# S6.net
KiCad netlist of a schematic drawn in Altium Designer
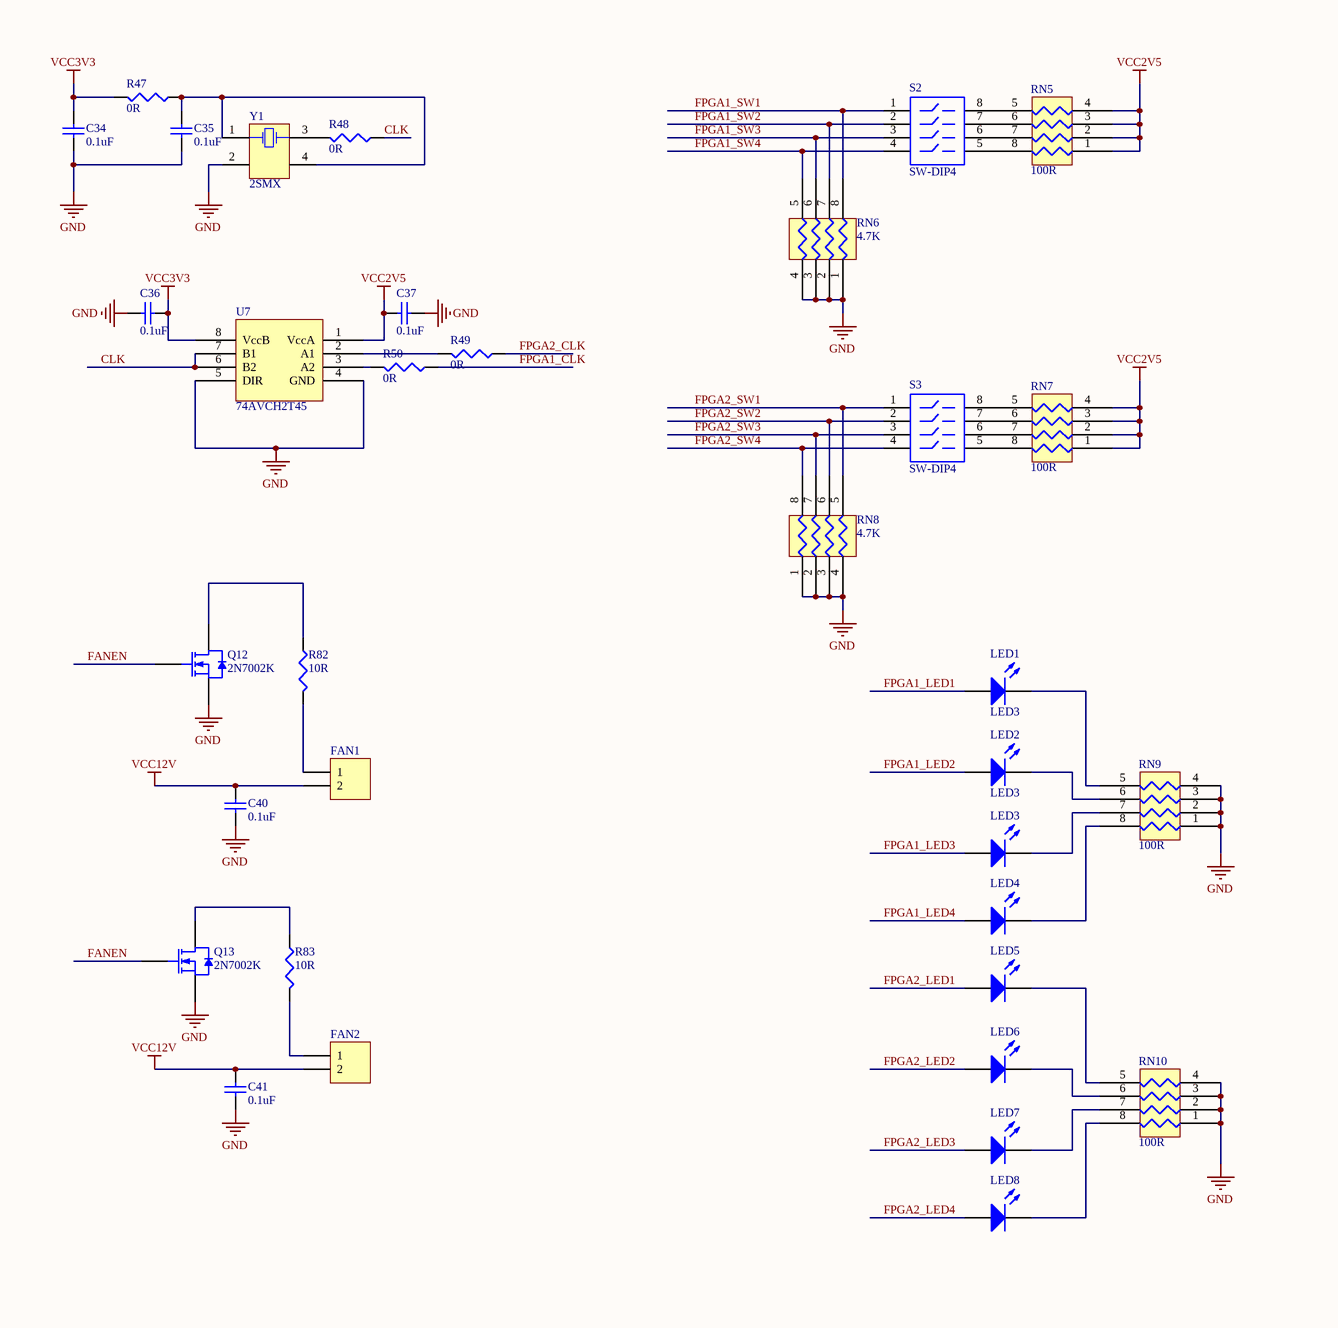
[diagram p0: S6.SchDoc, left]
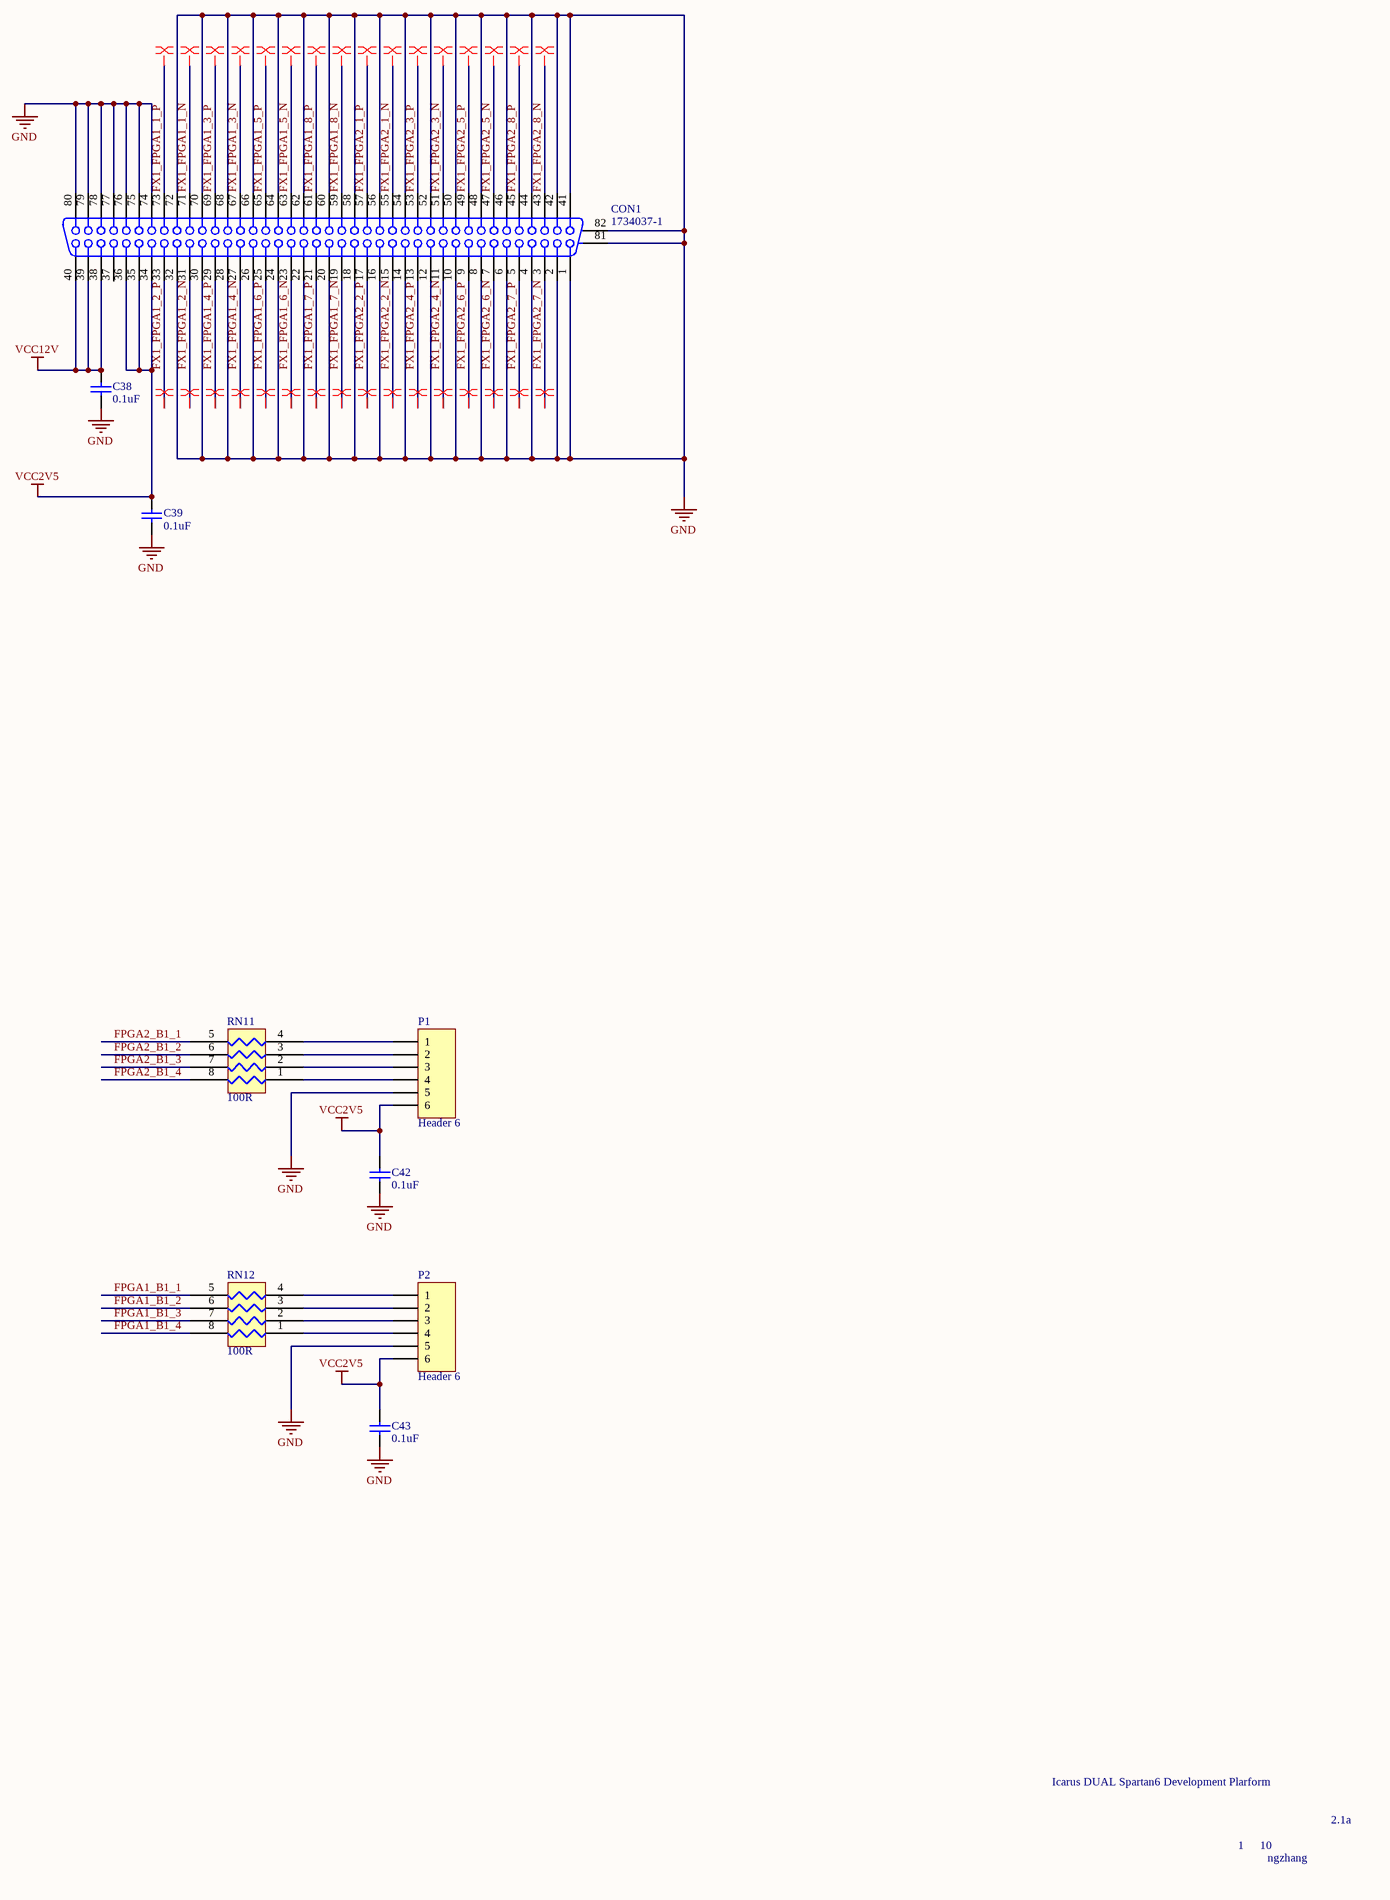
[diagram p1: S6.SchDoc, right]

(export (version "E")
  (design (tool "Eeschema 10.0.6"))
  (components
    (comp (ref "C34")
      (value "0.1uF")
      (footprint "1608[0603]")
      (description "Capacitor (Semiconductor SIM Model)")
      (fields (field (name "PUBLISHER") "Altium Limited"))
      (libsource (lib "Miscellaneous Devices") (part "Cap Semi"))
    )
    (comp (ref "C35")
      (value "0.1uF")
      (footprint "1608[0603]")
      (description "Capacitor (Semiconductor SIM Model)")
      (fields (field (name "PUBLISHER") "Altium Limited"))
      (libsource (lib "Miscellaneous Devices") (part "Cap Semi"))
    )
    (comp (ref "C36")
      (value "0.1uF")
      (footprint "1608[0603]")
      (description "Capacitor (Semiconductor SIM Model)")
      (fields (field (name "PUBLISHER") "Altium Limited"))
      (libsource (lib "Miscellaneous Devices") (part "Cap Semi"))
    )
    (comp (ref "C37")
      (value "0.1uF")
      (footprint "1608[0603]")
      (description "Capacitor (Semiconductor SIM Model)")
      (fields (field (name "PUBLISHER") "Altium Limited"))
      (libsource (lib "Miscellaneous Devices") (part "Cap Semi"))
    )
    (comp (ref "C38")
      (value "0.1uF")
      (footprint "1608[0603]")
      (description "Capacitor (Semiconductor SIM Model)")
      (fields (field (name "PUBLISHER") "Altium Limited"))
      (libsource (lib "Miscellaneous Devices") (part "Cap Semi"))
    )
    (comp (ref "C39")
      (value "0.1uF")
      (footprint "1608[0603]")
      (description "Capacitor (Semiconductor SIM Model)")
      (fields (field (name "PUBLISHER") "Altium Limited"))
      (libsource (lib "Miscellaneous Devices") (part "Cap Semi"))
    )
    (comp (ref "C40")
      (value "0.1uF")
      (footprint "1608[0603]")
      (description "Capacitor (Semiconductor SIM Model)")
      (fields (field (name "PUBLISHER") "Altium Limited"))
      (libsource (lib "Miscellaneous Devices") (part "Cap Semi"))
    )
    (comp (ref "C41")
      (value "0.1uF")
      (footprint "1608[0603]")
      (description "Capacitor (Semiconductor SIM Model)")
      (fields (field (name "PUBLISHER") "Altium Limited"))
      (libsource (lib "Miscellaneous Devices") (part "Cap Semi"))
    )
    (comp (ref "C42")
      (value "0.1uF")
      (footprint "1608[0603]")
      (description "Capacitor (Semiconductor SIM Model)")
      (fields (field (name "PUBLISHER") "Altium Limited"))
      (libsource (lib "Miscellaneous Devices") (part "Cap Semi"))
    )
    (comp (ref "C43")
      (value "0.1uF")
      (footprint "1608[0603]")
      (description "Capacitor (Semiconductor SIM Model)")
      (fields (field (name "PUBLISHER") "Altium Limited"))
      (libsource (lib "Miscellaneous Devices") (part "Cap Semi"))
    )
    (comp (ref "CON1") (value "1734037-1") (footprint "1734037-1") (libsource (lib "S6") (part "1734037-1")))
    (comp (ref "FAN1")
      (value "Header 2")
      (footprint "2PINFAN")
      (description "Header, 2-Pin")
      (fields (field (name "PUBLISHER") "Altium Limited"))
      (libsource (lib "Miscellaneous Connectors") (part "Header 2"))
    )
    (comp (ref "FAN2")
      (value "Header 2")
      (footprint "2PINFAN")
      (description "Header, 2-Pin")
      (fields (field (name "PUBLISHER") "Altium Limited"))
      (libsource (lib "Miscellaneous Connectors") (part "Header 2"))
    )
    (comp (ref "LED1")
      (value "LED3")
      (footprint "CD1608-0603")
      (description "Typical BLUE SiC LED")
      (fields (field (name "PUBLISHER") "Altium Limited"))
      (libsource (lib "Miscellaneous Devices") (part "LED3"))
    )
    (comp (ref "LED2")
      (value "LED3")
      (footprint "CD1608-0603")
      (description "Typical BLUE SiC LED")
      (fields (field (name "PUBLISHER") "Altium Limited"))
      (libsource (lib "Miscellaneous Devices") (part "LED3"))
    )
    (comp (ref "LED3")
      (value "LED3")
      (footprint "CD1608-0603")
      (description "Typical BLUE SiC LED")
      (fields (field (name "PUBLISHER") "Altium Limited"))
      (libsource (lib "Miscellaneous Devices") (part "LED3"))
    )
    (comp (ref "LED4")
      (value "LED3")
      (footprint "CD1608-0603")
      (description "Typical BLUE SiC LED")
      (fields (field (name "PUBLISHER") "Altium Limited"))
      (libsource (lib "Miscellaneous Devices") (part "LED3"))
    )
    (comp (ref "LED5")
      (value "LED3")
      (footprint "CD1608-0603")
      (description "Typical BLUE SiC LED")
      (fields (field (name "PUBLISHER") "Altium Limited"))
      (libsource (lib "Miscellaneous Devices") (part "LED3"))
    )
    (comp (ref "LED6")
      (value "LED3")
      (footprint "CD1608-0603")
      (description "Typical BLUE SiC LED")
      (fields (field (name "PUBLISHER") "Altium Limited"))
      (libsource (lib "Miscellaneous Devices") (part "LED3"))
    )
    (comp (ref "LED7")
      (value "LED3")
      (footprint "CD1608-0603")
      (description "Typical BLUE SiC LED")
      (fields (field (name "PUBLISHER") "Altium Limited"))
      (libsource (lib "Miscellaneous Devices") (part "LED3"))
    )
    (comp (ref "LED8")
      (value "LED3")
      (footprint "CD1608-0603")
      (description "Typical BLUE SiC LED")
      (fields (field (name "PUBLISHER") "Altium Limited"))
      (libsource (lib "Miscellaneous Devices") (part "LED3"))
    )
    (comp (ref "P1")
      (value "Header 6")
      (footprint "HDR1X6")
      (description "Header, 6-Pin")
      (fields (field (name "PUBLISHER") "Altium Limited"))
      (libsource (lib "Miscellaneous Connectors") (part "Header 6"))
    )
    (comp (ref "P2")
      (value "Header 6")
      (footprint "HDR1X6")
      (description "Header, 6-Pin")
      (fields (field (name "PUBLISHER") "Altium Limited"))
      (libsource (lib "Miscellaneous Connectors") (part "Header 6"))
    )
    (comp (ref "Q12")
      (value "2N7002K")
      (footprint "SOT23_N")
      (description "N-channel Enhancement Mode Field-effect Transistor")
      (fields (field (name "PUBLISHER") "Altium Limited"))
      (libsource (lib "Philips Discrete MOSFET - Low Power") (part "2N7002"))
    )
    (comp (ref "Q13")
      (value "2N7002K")
      (footprint "SOT23_N")
      (description "N-channel Enhancement Mode Field-effect Transistor")
      (fields (field (name "PUBLISHER") "Altium Limited"))
      (libsource (lib "Philips Discrete MOSFET - Low Power") (part "2N7002"))
    )
    (comp (ref "R47")
      (value "0R")
      (footprint "J1-0603")
      (description "Resistor")
      (fields (field (name "PUBLISHER") "Altium Limited"))
      (libsource (lib "Miscellaneous Devices") (part "Res3"))
    )
    (comp (ref "R48")
      (value "0R")
      (footprint "J1-0603")
      (description "Resistor")
      (fields (field (name "PUBLISHER") "Altium Limited"))
      (libsource (lib "Miscellaneous Devices") (part "Res3"))
    )
    (comp (ref "R49")
      (value "0R")
      (footprint "J1-0603")
      (description "Resistor")
      (fields (field (name "PUBLISHER") "Altium Limited"))
      (libsource (lib "Miscellaneous Devices") (part "Res3"))
    )
    (comp (ref "R50")
      (value "0R")
      (footprint "J1-0603")
      (description "Resistor")
      (fields (field (name "PUBLISHER") "Altium Limited"))
      (libsource (lib "Miscellaneous Devices") (part "Res3"))
    )
    (comp (ref "R82")
      (value "10R")
      (footprint "J1-0603")
      (description "Resistor")
      (fields (field (name "PUBLISHER") "Altium Limited"))
      (libsource (lib "Miscellaneous Devices") (part "Res3"))
    )
    (comp (ref "R83")
      (value "10R")
      (footprint "J1-0603")
      (description "Resistor")
      (fields (field (name "PUBLISHER") "Altium Limited"))
      (libsource (lib "Miscellaneous Devices") (part "Res3"))
    )
    (comp (ref "RN5") (value "100R") (footprint "EXBV8V") (libsource (lib "S6") (part "RES4PACK")))
    (comp (ref "RN6") (value "4.7K") (footprint "EXBV8V") (libsource (lib "") (part "RES4PACK_2")))
    (comp (ref "RN7") (value "100R") (footprint "EXBV8V") (libsource (lib "S6") (part "RES4PACK")))
    (comp (ref "RN8") (value "4.7K") (footprint "EXBV8V") (libsource (lib "") (part "RES4PACK_1")))
    (comp (ref "RN9") (value "100R") (footprint "EXBV8V") (libsource (lib "S6") (part "RES4PACK")))
    (comp (ref "RN10") (value "100R") (footprint "EXBV8V") (libsource (lib "S6") (part "RES4PACK")))
    (comp (ref "RN11") (value "100R") (footprint "EXBV8V") (libsource (lib "S6") (part "RES4PACK")))
    (comp (ref "RN12") (value "100R") (footprint "EXBV8V") (libsource (lib "S6") (part "RES4PACK")))
    (comp (ref "S2")
      (value "SW-DIP4")
      (footprint "SO8_N")
      (description "DIP Switch")
      (fields (field (name "PUBLISHER") "Altium Limited"))
      (libsource (lib "Miscellaneous Devices") (part "SW-DIP4"))
    )
    (comp (ref "S3")
      (value "SW-DIP4")
      (footprint "SO8_N")
      (description "DIP Switch")
      (fields (field (name "PUBLISHER") "Altium Limited"))
      (libsource (lib "Miscellaneous Devices") (part "SW-DIP4"))
    )
    (comp (ref "U7") (value "74AVCH2T45") (footprint "SOT765-1") (libsource (lib "S6") (part "74AVCH2T45")))
    (comp (ref "Y1")
      (value "2SMX")
      (footprint "SMX2")
      (description "Surface Mount Quartz Crystal")
      (fields (field (name "PUBLISHER") "Altium Limited"))
      (libsource (lib "C-MAC Crystal Oscillator") (part "2SMX"))
    )
  )
  (nets
    (net (code "1") (name "/CLK") (class "Default")
      (node (ref "R48") (pin "1") (pinfunction "1_1") (pintype "passive"))
      (node (ref "U7") (pin "6") (pinfunction "B2_6") (pintype "passive"))
      (node (ref "U7") (pin "7") (pinfunction "B1_7") (pintype "passive"))
    )
    (net (code "2") (name "/FANEN") (class "Default")
      (node (ref "Q12") (pin "1") (pinfunction "G_1") (pintype "passive"))
      (node (ref "Q13") (pin "1") (pinfunction "G_1") (pintype "passive"))
    )
    (net (code "3") (name "/FPGA1_B1_1") (class "Default")
      (node (ref "RN12") (pin "5") (pinfunction "5_5") (pintype "power_in"))
    )
    (net (code "4") (name "/FPGA1_B1_2") (class "Default")
      (node (ref "RN12") (pin "6") (pinfunction "6_6") (pintype "power_in"))
    )
    (net (code "5") (name "/FPGA1_B1_3") (class "Default")
      (node (ref "RN12") (pin "7") (pinfunction "7_7") (pintype "power_in"))
    )
    (net (code "6") (name "/FPGA1_B1_4") (class "Default")
      (node (ref "RN12") (pin "8") (pinfunction "8_8") (pintype "power_in"))
    )
    (net (code "7") (name "/FPGA1_CLK") (class "Default")
      (node (ref "R50") (pin "1") (pinfunction "1_1") (pintype "passive"))
    )
    (net (code "8") (name "/FPGA1_LED1") (class "Default")
      (node (ref "LED1") (pin "1") (pinfunction "A_1") (pintype "passive"))
    )
    (net (code "9") (name "/FPGA1_LED2") (class "Default")
      (node (ref "LED2") (pin "1") (pinfunction "A_1") (pintype "passive"))
    )
    (net (code "10") (name "/FPGA1_LED3") (class "Default")
      (node (ref "LED3") (pin "1") (pinfunction "A_1") (pintype "passive"))
    )
    (net (code "11") (name "/FPGA1_LED4") (class "Default")
      (node (ref "LED4") (pin "1") (pinfunction "A_1") (pintype "passive"))
    )
    (net (code "12") (name "/FPGA1_SW1") (class "Default")
      (node (ref "RN6") (pin "8") (pinfunction "8_8") (pintype "power_in"))
      (node (ref "S2") (pin "1") (pinfunction "1_1") (pintype "passive"))
    )
    (net (code "13") (name "/FPGA1_SW2") (class "Default")
      (node (ref "RN6") (pin "7") (pinfunction "7_7") (pintype "power_in"))
      (node (ref "S2") (pin "2") (pinfunction "2_2") (pintype "passive"))
    )
    (net (code "14") (name "/FPGA1_SW3") (class "Default")
      (node (ref "RN6") (pin "6") (pinfunction "6_6") (pintype "power_in"))
      (node (ref "S2") (pin "3") (pinfunction "3_3") (pintype "passive"))
    )
    (net (code "15") (name "/FPGA1_SW4") (class "Default")
      (node (ref "RN6") (pin "5") (pinfunction "5_5") (pintype "power_in"))
      (node (ref "S2") (pin "4") (pinfunction "4_4") (pintype "passive"))
    )
    (net (code "16") (name "/FPGA2_B1_1") (class "Default")
      (node (ref "RN11") (pin "5") (pinfunction "5_5") (pintype "power_in"))
    )
    (net (code "17") (name "/FPGA2_B1_2") (class "Default")
      (node (ref "RN11") (pin "6") (pinfunction "6_6") (pintype "power_in"))
    )
    (net (code "18") (name "/FPGA2_B1_3") (class "Default")
      (node (ref "RN11") (pin "7") (pinfunction "7_7") (pintype "power_in"))
    )
    (net (code "19") (name "/FPGA2_B1_4") (class "Default")
      (node (ref "RN11") (pin "8") (pinfunction "8_8") (pintype "power_in"))
    )
    (net (code "20") (name "/FPGA2_CLK") (class "Default")
      (node (ref "R49") (pin "1") (pinfunction "1_1") (pintype "passive"))
    )
    (net (code "21") (name "/FPGA2_LED1") (class "Default")
      (node (ref "LED5") (pin "1") (pinfunction "A_1") (pintype "passive"))
    )
    (net (code "22") (name "/FPGA2_LED2") (class "Default")
      (node (ref "LED6") (pin "1") (pinfunction "A_1") (pintype "passive"))
    )
    (net (code "23") (name "/FPGA2_LED3") (class "Default")
      (node (ref "LED7") (pin "1") (pinfunction "A_1") (pintype "passive"))
    )
    (net (code "24") (name "/FPGA2_LED4") (class "Default")
      (node (ref "LED8") (pin "1") (pinfunction "A_1") (pintype "passive"))
    )
    (net (code "25") (name "/FPGA2_SW1") (class "Default")
      (node (ref "RN8") (pin "5") (pinfunction "5_5") (pintype "power_in"))
      (node (ref "S3") (pin "1") (pinfunction "1_1") (pintype "passive"))
    )
    (net (code "26") (name "/FPGA2_SW2") (class "Default")
      (node (ref "RN8") (pin "6") (pinfunction "6_6") (pintype "power_in"))
      (node (ref "S3") (pin "2") (pinfunction "2_2") (pintype "passive"))
    )
    (net (code "27") (name "/FPGA2_SW3") (class "Default")
      (node (ref "RN8") (pin "7") (pinfunction "7_7") (pintype "power_in"))
      (node (ref "S3") (pin "3") (pinfunction "3_3") (pintype "passive"))
    )
    (net (code "28") (name "/FPGA2_SW4") (class "Default")
      (node (ref "RN8") (pin "8") (pinfunction "8_8") (pintype "power_in"))
      (node (ref "S3") (pin "4") (pinfunction "4_4") (pintype "passive"))
    )
    (net (code "29") (name "/FX1_FPGA1_1_N") (class "Default")
      (node (ref "CON1") (pin "71") (pinfunction "71_71") (pintype "passive"))
    )
    (net (code "30") (name "/FX1_FPGA1_1_P") (class "Default")
      (node (ref "CON1") (pin "73") (pinfunction "73_73") (pintype "passive"))
    )
    (net (code "31") (name "/FX1_FPGA1_2_N") (class "Default")
      (node (ref "CON1") (pin "31") (pinfunction "31_31") (pintype "passive"))
    )
    (net (code "32") (name "/FX1_FPGA1_2_P") (class "Default")
      (node (ref "CON1") (pin "33") (pinfunction "33_33") (pintype "passive"))
    )
    (net (code "33") (name "/FX1_FPGA1_3_N") (class "Default")
      (node (ref "CON1") (pin "67") (pinfunction "67_67") (pintype "passive"))
    )
    (net (code "34") (name "/FX1_FPGA1_3_P") (class "Default")
      (node (ref "CON1") (pin "69") (pinfunction "69_69") (pintype "passive"))
    )
    (net (code "35") (name "/FX1_FPGA1_4_N") (class "Default")
      (node (ref "CON1") (pin "27") (pinfunction "27_27") (pintype "passive"))
    )
    (net (code "36") (name "/FX1_FPGA1_4_P") (class "Default")
      (node (ref "CON1") (pin "29") (pinfunction "29_29") (pintype "passive"))
    )
    (net (code "37") (name "/FX1_FPGA1_5_N") (class "Default")
      (node (ref "CON1") (pin "63") (pinfunction "63_63") (pintype "passive"))
    )
    (net (code "38") (name "/FX1_FPGA1_5_P") (class "Default")
      (node (ref "CON1") (pin "65") (pinfunction "65_65") (pintype "passive"))
    )
    (net (code "39") (name "/FX1_FPGA1_6_N") (class "Default")
      (node (ref "CON1") (pin "23") (pinfunction "23_23") (pintype "passive"))
    )
    (net (code "40") (name "/FX1_FPGA1_6_P") (class "Default")
      (node (ref "CON1") (pin "25") (pinfunction "25_25") (pintype "passive"))
    )
    (net (code "41") (name "/FX1_FPGA1_7_N") (class "Default")
      (node (ref "CON1") (pin "19") (pinfunction "19_19") (pintype "passive"))
    )
    (net (code "42") (name "/FX1_FPGA1_7_P") (class "Default")
      (node (ref "CON1") (pin "21") (pinfunction "21_21") (pintype "passive"))
    )
    (net (code "43") (name "/FX1_FPGA1_8_N") (class "Default")
      (node (ref "CON1") (pin "59") (pinfunction "59_59") (pintype "passive"))
    )
    (net (code "44") (name "/FX1_FPGA1_8_P") (class "Default")
      (node (ref "CON1") (pin "61") (pinfunction "61_61") (pintype "passive"))
    )
    (net (code "45") (name "/FX1_FPGA2_1_N") (class "Default")
      (node (ref "CON1") (pin "55") (pinfunction "55_55") (pintype "passive"))
    )
    (net (code "46") (name "/FX1_FPGA2_1_P") (class "Default")
      (node (ref "CON1") (pin "57") (pinfunction "57_57") (pintype "passive"))
    )
    (net (code "47") (name "/FX1_FPGA2_2_N") (class "Default")
      (node (ref "CON1") (pin "15") (pinfunction "15_15") (pintype "passive"))
    )
    (net (code "48") (name "/FX1_FPGA2_2_P") (class "Default")
      (node (ref "CON1") (pin "17") (pinfunction "17_17") (pintype "passive"))
    )
    (net (code "49") (name "/FX1_FPGA2_3_N") (class "Default")
      (node (ref "CON1") (pin "51") (pinfunction "51_51") (pintype "passive"))
    )
    (net (code "50") (name "/FX1_FPGA2_3_P") (class "Default")
      (node (ref "CON1") (pin "53") (pinfunction "53_53") (pintype "passive"))
    )
    (net (code "51") (name "/FX1_FPGA2_4_N") (class "Default")
      (node (ref "CON1") (pin "11") (pinfunction "11_11") (pintype "passive"))
    )
    (net (code "52") (name "/FX1_FPGA2_4_P") (class "Default")
      (node (ref "CON1") (pin "13") (pinfunction "13_13") (pintype "passive"))
    )
    (net (code "53") (name "/FX1_FPGA2_5_N") (class "Default")
      (node (ref "CON1") (pin "47") (pinfunction "47_47") (pintype "passive"))
    )
    (net (code "54") (name "/FX1_FPGA2_5_P") (class "Default")
      (node (ref "CON1") (pin "49") (pinfunction "49_49") (pintype "passive"))
    )
    (net (code "55") (name "/FX1_FPGA2_6_N") (class "Default")
      (node (ref "CON1") (pin "7") (pinfunction "7_7") (pintype "passive"))
    )
    (net (code "56") (name "/FX1_FPGA2_6_P") (class "Default")
      (node (ref "CON1") (pin "9") (pinfunction "9_9") (pintype "passive"))
    )
    (net (code "57") (name "/FX1_FPGA2_7_N") (class "Default")
      (node (ref "CON1") (pin "3") (pinfunction "3_3") (pintype "passive"))
    )
    (net (code "58") (name "/FX1_FPGA2_7_P") (class "Default")
      (node (ref "CON1") (pin "5") (pinfunction "5_5") (pintype "passive"))
    )
    (net (code "59") (name "/FX1_FPGA2_8_N") (class "Default")
      (node (ref "CON1") (pin "43") (pinfunction "43_43") (pintype "passive"))
    )
    (net (code "60") (name "/FX1_FPGA2_8_P") (class "Default")
      (node (ref "CON1") (pin "45") (pinfunction "45_45") (pintype "passive"))
    )
    (net (code "61") (name "GND") (class "Default")
      (node (ref "C34") (pin "1") (pinfunction "1_1") (pintype "passive"))
      (node (ref "C35") (pin "1") (pinfunction "1_1") (pintype "passive"))
      (node (ref "C36") (pin "2") (pinfunction "2_2") (pintype "passive"))
      (node (ref "C37") (pin "1") (pinfunction "1_1") (pintype "passive"))
      (node (ref "C38") (pin "1") (pinfunction "1_1") (pintype "passive"))
      (node (ref "C39") (pin "1") (pinfunction "1_1") (pintype "passive"))
      (node (ref "C40") (pin "2") (pinfunction "2_2") (pintype "passive"))
      (node (ref "C41") (pin "2") (pinfunction "2_2") (pintype "passive"))
      (node (ref "C42") (pin "1") (pinfunction "1_1") (pintype "passive"))
      (node (ref "C43") (pin "1") (pinfunction "1_1") (pintype "passive"))
      (node (ref "CON1") (pin "1") (pinfunction "1_1") (pintype "passive"))
      (node (ref "CON1") (pin "10") (pinfunction "10_10") (pintype "passive"))
      (node (ref "CON1") (pin "12") (pinfunction "12_12") (pintype "passive"))
      (node (ref "CON1") (pin "14") (pinfunction "14_14") (pintype "passive"))
      (node (ref "CON1") (pin "16") (pinfunction "16_16") (pintype "passive"))
      (node (ref "CON1") (pin "18") (pinfunction "18_18") (pintype "passive"))
      (node (ref "CON1") (pin "2") (pinfunction "2_2") (pintype "passive"))
      (node (ref "CON1") (pin "20") (pinfunction "20_20") (pintype "passive"))
      (node (ref "CON1") (pin "22") (pinfunction "22_22") (pintype "passive"))
      (node (ref "CON1") (pin "24") (pinfunction "24_24") (pintype "passive"))
      (node (ref "CON1") (pin "26") (pinfunction "26_26") (pintype "passive"))
      (node (ref "CON1") (pin "28") (pinfunction "28_28") (pintype "passive"))
      (node (ref "CON1") (pin "30") (pinfunction "30_30") (pintype "passive"))
      (node (ref "CON1") (pin "32") (pinfunction "32_32") (pintype "passive"))
      (node (ref "CON1") (pin "4") (pinfunction "4_4") (pintype "passive"))
      (node (ref "CON1") (pin "41") (pinfunction "41_41") (pintype "passive"))
      (node (ref "CON1") (pin "42") (pinfunction "42_42") (pintype "passive"))
      (node (ref "CON1") (pin "44") (pinfunction "44_44") (pintype "passive"))
      (node (ref "CON1") (pin "46") (pinfunction "46_46") (pintype "passive"))
      (node (ref "CON1") (pin "48") (pinfunction "48_48") (pintype "passive"))
      (node (ref "CON1") (pin "50") (pinfunction "50_50") (pintype "passive"))
      (node (ref "CON1") (pin "52") (pinfunction "52_52") (pintype "passive"))
      (node (ref "CON1") (pin "54") (pinfunction "54_54") (pintype "passive"))
      (node (ref "CON1") (pin "56") (pinfunction "56_56") (pintype "passive"))
      (node (ref "CON1") (pin "58") (pinfunction "58_58") (pintype "passive"))
      (node (ref "CON1") (pin "6") (pinfunction "6_6") (pintype "passive"))
      (node (ref "CON1") (pin "60") (pinfunction "60_60") (pintype "passive"))
      (node (ref "CON1") (pin "62") (pinfunction "62_62") (pintype "passive"))
      (node (ref "CON1") (pin "64") (pinfunction "64_64") (pintype "passive"))
      (node (ref "CON1") (pin "66") (pinfunction "66_66") (pintype "passive"))
      (node (ref "CON1") (pin "68") (pinfunction "68_68") (pintype "passive"))
      (node (ref "CON1") (pin "70") (pinfunction "70_70") (pintype "passive"))
      (node (ref "CON1") (pin "72") (pinfunction "72_72") (pintype "passive"))
      (node (ref "CON1") (pin "74") (pinfunction "74_74") (pintype "passive"))
      (node (ref "CON1") (pin "75") (pinfunction "75_75") (pintype "passive"))
      (node (ref "CON1") (pin "76") (pinfunction "76_76") (pintype "passive"))
      (node (ref "CON1") (pin "77") (pinfunction "77_77") (pintype "passive"))
      (node (ref "CON1") (pin "78") (pinfunction "78_78") (pintype "passive"))
      (node (ref "CON1") (pin "79") (pinfunction "79_79") (pintype "passive"))
      (node (ref "CON1") (pin "8") (pinfunction "8_8") (pintype "passive"))
      (node (ref "CON1") (pin "80") (pinfunction "80_80") (pintype "passive"))
      (node (ref "CON1") (pin "81") (pinfunction "MH1_81") (pintype "passive"))
      (node (ref "CON1") (pin "82") (pinfunction "MH2_82") (pintype "passive"))
      (node (ref "P1") (pin "5") (pinfunction "5_5") (pintype "passive"))
      (node (ref "P2") (pin "5") (pinfunction "5_5") (pintype "passive"))
      (node (ref "Q12") (pin "2") (pinfunction "S_2") (pintype "passive"))
      (node (ref "Q13") (pin "2") (pinfunction "S_2") (pintype "passive"))
      (node (ref "RN10") (pin "1") (pinfunction "1_1") (pintype "power_in"))
      (node (ref "RN10") (pin "2") (pinfunction "2_2") (pintype "power_in"))
      (node (ref "RN10") (pin "3") (pinfunction "3_3") (pintype "power_in"))
      (node (ref "RN10") (pin "4") (pinfunction "4_4") (pintype "power_in"))
      (node (ref "RN6") (pin "1") (pinfunction "1_1") (pintype "power_in"))
      (node (ref "RN6") (pin "2") (pinfunction "2_2") (pintype "power_in"))
      (node (ref "RN6") (pin "3") (pinfunction "3_3") (pintype "power_in"))
      (node (ref "RN6") (pin "4") (pinfunction "4_4") (pintype "power_in"))
      (node (ref "RN8") (pin "1") (pinfunction "1_1") (pintype "power_in"))
      (node (ref "RN8") (pin "2") (pinfunction "2_2") (pintype "power_in"))
      (node (ref "RN8") (pin "3") (pinfunction "3_3") (pintype "power_in"))
      (node (ref "RN8") (pin "4") (pinfunction "4_4") (pintype "power_in"))
      (node (ref "RN9") (pin "1") (pinfunction "1_1") (pintype "power_in"))
      (node (ref "RN9") (pin "2") (pinfunction "2_2") (pintype "power_in"))
      (node (ref "RN9") (pin "3") (pinfunction "3_3") (pintype "power_in"))
      (node (ref "RN9") (pin "4") (pinfunction "4_4") (pintype "power_in"))
      (node (ref "U7") (pin "4") (pinfunction "GND_4") (pintype "passive"))
      (node (ref "U7") (pin "5") (pinfunction "DIR_5") (pintype "passive"))
      (node (ref "Y1") (pin "2") (pinfunction "NC_2") (pintype "passive"))
    )
    (net (code "62") (name "Net-(FAN1-Pad1)") (class "Default")
      (node (ref "FAN1") (pin "1") (pinfunction "1_1") (pintype "passive"))
      (node (ref "R82") (pin "2") (pinfunction "2_2") (pintype "passive"))
    )
    (net (code "63") (name "Net-(FAN2-Pad1)") (class "Default")
      (node (ref "FAN2") (pin "1") (pinfunction "1_1") (pintype "passive"))
      (node (ref "R83") (pin "2") (pinfunction "2_2") (pintype "passive"))
    )
    (net (code "64") (name "Net-(LED1-K)") (class "Default")
      (node (ref "LED1") (pin "2") (pinfunction "K_2") (pintype "passive"))
      (node (ref "RN9") (pin "5") (pinfunction "5_5") (pintype "power_in"))
    )
    (net (code "65") (name "Net-(LED2-K)") (class "Default")
      (node (ref "LED2") (pin "2") (pinfunction "K_2") (pintype "passive"))
      (node (ref "RN9") (pin "6") (pinfunction "6_6") (pintype "power_in"))
    )
    (net (code "66") (name "Net-(LED3-K)") (class "Default")
      (node (ref "LED3") (pin "2") (pinfunction "K_2") (pintype "passive"))
      (node (ref "RN9") (pin "7") (pinfunction "7_7") (pintype "power_in"))
    )
    (net (code "67") (name "Net-(LED4-K)") (class "Default")
      (node (ref "LED4") (pin "2") (pinfunction "K_2") (pintype "passive"))
      (node (ref "RN9") (pin "8") (pinfunction "8_8") (pintype "power_in"))
    )
    (net (code "68") (name "Net-(LED5-K)") (class "Default")
      (node (ref "LED5") (pin "2") (pinfunction "K_2") (pintype "passive"))
      (node (ref "RN10") (pin "5") (pinfunction "5_5") (pintype "power_in"))
    )
    (net (code "69") (name "Net-(LED6-K)") (class "Default")
      (node (ref "LED6") (pin "2") (pinfunction "K_2") (pintype "passive"))
      (node (ref "RN10") (pin "6") (pinfunction "6_6") (pintype "power_in"))
    )
    (net (code "70") (name "Net-(LED7-K)") (class "Default")
      (node (ref "LED7") (pin "2") (pinfunction "K_2") (pintype "passive"))
      (node (ref "RN10") (pin "7") (pinfunction "7_7") (pintype "power_in"))
    )
    (net (code "71") (name "Net-(LED8-K)") (class "Default")
      (node (ref "LED8") (pin "2") (pinfunction "K_2") (pintype "passive"))
      (node (ref "RN10") (pin "8") (pinfunction "8_8") (pintype "power_in"))
    )
    (net (code "72") (name "Net-(P1-Pad1)") (class "Default")
      (node (ref "P1") (pin "1") (pinfunction "1_1") (pintype "passive"))
      (node (ref "RN11") (pin "4") (pinfunction "4_4") (pintype "power_in"))
    )
    (net (code "73") (name "Net-(P1-Pad2)") (class "Default")
      (node (ref "P1") (pin "2") (pinfunction "2_2") (pintype "passive"))
      (node (ref "RN11") (pin "3") (pinfunction "3_3") (pintype "power_in"))
    )
    (net (code "74") (name "Net-(P1-Pad3)") (class "Default")
      (node (ref "P1") (pin "3") (pinfunction "3_3") (pintype "passive"))
      (node (ref "RN11") (pin "2") (pinfunction "2_2") (pintype "power_in"))
    )
    (net (code "75") (name "Net-(P1-Pad4)") (class "Default")
      (node (ref "P1") (pin "4") (pinfunction "4_4") (pintype "passive"))
      (node (ref "RN11") (pin "1") (pinfunction "1_1") (pintype "power_in"))
    )
    (net (code "76") (name "Net-(P2-Pad1)") (class "Default")
      (node (ref "P2") (pin "1") (pinfunction "1_1") (pintype "passive"))
      (node (ref "RN12") (pin "4") (pinfunction "4_4") (pintype "power_in"))
    )
    (net (code "77") (name "Net-(P2-Pad2)") (class "Default")
      (node (ref "P2") (pin "2") (pinfunction "2_2") (pintype "passive"))
      (node (ref "RN12") (pin "3") (pinfunction "3_3") (pintype "power_in"))
    )
    (net (code "78") (name "Net-(P2-Pad3)") (class "Default")
      (node (ref "P2") (pin "3") (pinfunction "3_3") (pintype "passive"))
      (node (ref "RN12") (pin "2") (pinfunction "2_2") (pintype "power_in"))
    )
    (net (code "79") (name "Net-(P2-Pad4)") (class "Default")
      (node (ref "P2") (pin "4") (pinfunction "4_4") (pintype "passive"))
      (node (ref "RN12") (pin "1") (pinfunction "1_1") (pintype "power_in"))
    )
    (net (code "80") (name "Net-(Q12-D)") (class "Default")
      (node (ref "Q12") (pin "3") (pinfunction "D_3") (pintype "passive"))
      (node (ref "R82") (pin "1") (pinfunction "1_1") (pintype "passive"))
    )
    (net (code "81") (name "Net-(Q13-D)") (class "Default")
      (node (ref "Q13") (pin "3") (pinfunction "D_3") (pintype "passive"))
      (node (ref "R83") (pin "1") (pinfunction "1_1") (pintype "passive"))
    )
    (net (code "82") (name "Net-(RN5-Pad5)") (class "Default")
      (node (ref "RN5") (pin "5") (pinfunction "5_5") (pintype "power_in"))
      (node (ref "S2") (pin "8") (pinfunction "8_8") (pintype "passive"))
    )
    (net (code "83") (name "Net-(RN5-Pad6)") (class "Default")
      (node (ref "RN5") (pin "6") (pinfunction "6_6") (pintype "power_in"))
      (node (ref "S2") (pin "7") (pinfunction "7_7") (pintype "passive"))
    )
    (net (code "84") (name "Net-(RN5-Pad7)") (class "Default")
      (node (ref "RN5") (pin "7") (pinfunction "7_7") (pintype "power_in"))
      (node (ref "S2") (pin "6") (pinfunction "6_6") (pintype "passive"))
    )
    (net (code "85") (name "Net-(RN5-Pad8)") (class "Default")
      (node (ref "RN5") (pin "8") (pinfunction "8_8") (pintype "power_in"))
      (node (ref "S2") (pin "5") (pinfunction "5_5") (pintype "passive"))
    )
    (net (code "86") (name "Net-(RN7-Pad5)") (class "Default")
      (node (ref "RN7") (pin "5") (pinfunction "5_5") (pintype "power_in"))
      (node (ref "S3") (pin "8") (pinfunction "8_8") (pintype "passive"))
    )
    (net (code "87") (name "Net-(RN7-Pad6)") (class "Default")
      (node (ref "RN7") (pin "6") (pinfunction "6_6") (pintype "power_in"))
      (node (ref "S3") (pin "7") (pinfunction "7_7") (pintype "passive"))
    )
    (net (code "88") (name "Net-(RN7-Pad7)") (class "Default")
      (node (ref "RN7") (pin "7") (pinfunction "7_7") (pintype "power_in"))
      (node (ref "S3") (pin "6") (pinfunction "6_6") (pintype "passive"))
    )
    (net (code "89") (name "Net-(RN7-Pad8)") (class "Default")
      (node (ref "RN7") (pin "8") (pinfunction "8_8") (pintype "power_in"))
      (node (ref "S3") (pin "5") (pinfunction "5_5") (pintype "passive"))
    )
    (net (code "90") (name "Net-(U7-A1)") (class "Default")
      (node (ref "R49") (pin "2") (pinfunction "2_2") (pintype "passive"))
      (node (ref "U7") (pin "2") (pinfunction "A1_2") (pintype "passive"))
    )
    (net (code "91") (name "Net-(U7-A2)") (class "Default")
      (node (ref "R50") (pin "2") (pinfunction "2_2") (pintype "passive"))
      (node (ref "U7") (pin "3") (pinfunction "A2_3") (pintype "passive"))
    )
    (net (code "92") (name "Net-(Y1-OSC1)") (class "Default")
      (node (ref "C35") (pin "2") (pinfunction "2_2") (pintype "passive"))
      (node (ref "R47") (pin "1") (pinfunction "1_1") (pintype "passive"))
      (node (ref "Y1") (pin "1") (pinfunction "OSC1_1") (pintype "passive"))
      (node (ref "Y1") (pin "4") (pinfunction "NC_4") (pintype "passive"))
    )
    (net (code "93") (name "Net-(Y1-OSC2)") (class "Default")
      (node (ref "R48") (pin "2") (pinfunction "2_2") (pintype "passive"))
      (node (ref "Y1") (pin "3") (pinfunction "OSC2_3") (pintype "passive"))
    )
    (net (code "94") (name "VCC2V5") (class "Default")
      (node (ref "C37") (pin "2") (pinfunction "2_2") (pintype "passive"))
      (node (ref "C39") (pin "2") (pinfunction "2_2") (pintype "passive"))
      (node (ref "C42") (pin "2") (pinfunction "2_2") (pintype "passive"))
      (node (ref "C43") (pin "2") (pinfunction "2_2") (pintype "passive"))
      (node (ref "CON1") (pin "34") (pinfunction "34_34") (pintype "passive"))
      (node (ref "CON1") (pin "35") (pinfunction "35_35") (pintype "passive"))
      (node (ref "CON1") (pin "36") (pinfunction "36_36") (pintype "passive"))
      (node (ref "P1") (pin "6") (pinfunction "6_6") (pintype "passive"))
      (node (ref "P2") (pin "6") (pinfunction "6_6") (pintype "passive"))
      (node (ref "RN5") (pin "1") (pinfunction "1_1") (pintype "power_in"))
      (node (ref "RN5") (pin "2") (pinfunction "2_2") (pintype "power_in"))
      (node (ref "RN5") (pin "3") (pinfunction "3_3") (pintype "power_in"))
      (node (ref "RN5") (pin "4") (pinfunction "4_4") (pintype "power_in"))
      (node (ref "RN7") (pin "1") (pinfunction "1_1") (pintype "power_in"))
      (node (ref "RN7") (pin "2") (pinfunction "2_2") (pintype "power_in"))
      (node (ref "RN7") (pin "3") (pinfunction "3_3") (pintype "power_in"))
      (node (ref "RN7") (pin "4") (pinfunction "4_4") (pintype "power_in"))
      (node (ref "U7") (pin "1") (pinfunction "VccA_1") (pintype "passive"))
    )
    (net (code "95") (name "VCC3V3") (class "Default")
      (node (ref "C34") (pin "2") (pinfunction "2_2") (pintype "passive"))
      (node (ref "C36") (pin "1") (pinfunction "1_1") (pintype "passive"))
      (node (ref "R47") (pin "2") (pinfunction "2_2") (pintype "passive"))
      (node (ref "U7") (pin "8") (pinfunction "VccB_8") (pintype "passive"))
    )
    (net (code "96") (name "VCC12V") (class "Default")
      (node (ref "C38") (pin "2") (pinfunction "2_2") (pintype "passive"))
      (node (ref "C40") (pin "1") (pinfunction "1_1") (pintype "passive"))
      (node (ref "C41") (pin "1") (pinfunction "1_1") (pintype "passive"))
      (node (ref "CON1") (pin "38") (pinfunction "38_38") (pintype "passive"))
      (node (ref "CON1") (pin "39") (pinfunction "39_39") (pintype "passive"))
      (node (ref "CON1") (pin "40") (pinfunction "40_40") (pintype "passive"))
      (node (ref "FAN1") (pin "2") (pinfunction "2_2") (pintype "passive"))
      (node (ref "FAN2") (pin "2") (pinfunction "2_2") (pintype "passive"))
    )
    (net (code "97") (name "unconnected-(CON1-Pad37)") (class "Default")
      (node (ref "CON1") (pin "37") (pinfunction "37_37") (pintype "passive"))
    )
  )
)
